# Solenoid_Drivers.net
KiCad netlist of a schematic drawn in Altium Designer
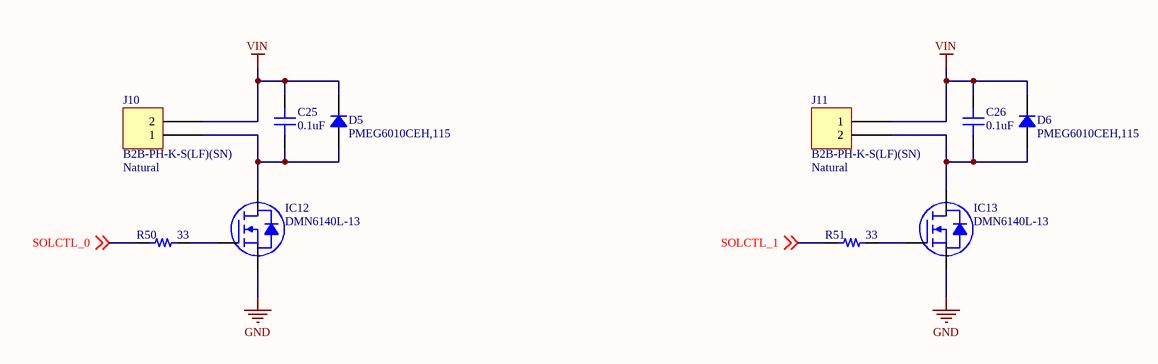
[diagram p0: Solenoid Drivers.SchDoc]

(export (version "E")
  (design (tool "Eeschema 10.0.6"))
  (components
    (comp (ref "C25")
      (value "0.1uF")
      (footprint "CAP 0603/1608")
      (description "CAP CER 0.1UF 50V X7R 0603")
      (fields
        (field (name "PART NUMBER") "CL10B104JB8NNNC")
        (field (name "MANUFACTURER") "Samsung Electro-Mechanics America, Inc.")
      )
      (libsource (lib "Celestial Library Database") (part "Capacitor"))
    )
    (comp (ref "C26")
      (value "0.1uF")
      (footprint "CAP 0603/1608")
      (description "CAP CER 0.1UF 50V X7R 0603")
      (fields
        (field (name "PART NUMBER") "CL10B104JB8NNNC")
        (field (name "MANUFACTURER") "Samsung Electro-Mechanics America, Inc.")
      )
      (libsource (lib "Celestial Library Database") (part "Capacitor"))
    )
    (comp (ref "D5")
      (value "PMEG6010CEH,115")
      (footprint "SOD123F")
      (description "DIODE SCHOTTKY 60V 1A SOD123F")
      (fields (field (name "MANUFACTURER") "NXP USA Inc."))
      (libsource (lib "Celestial Library Database") (part "Diode"))
    )
    (comp (ref "D6")
      (value "PMEG6010CEH,115")
      (footprint "SOD123F")
      (description "DIODE SCHOTTKY 60V 1A SOD123F")
      (fields (field (name "MANUFACTURER") "NXP USA Inc."))
      (libsource (lib "Celestial Library Database") (part "Diode"))
    )
    (comp (ref "IC12")
      (value "DMN6140L-13")
      (footprint "DIODES SOT-23-3")
      (description "MOSFET N-CH 60V 1.6A SOT23")
      (fields (field (name "MANUFACTURER") "Diodes Incorporated"))
      (libsource (lib "Celestial Library Database") (part "DIODES INC MOSFET N-CH SOT-23-3"))
    )
    (comp (ref "IC13")
      (value "DMN6140L-13")
      (footprint "DIODES SOT-23-3")
      (description "MOSFET N-CH 60V 1.6A SOT23")
      (fields (field (name "MANUFACTURER") "Diodes Incorporated"))
      (libsource (lib "Celestial Library Database") (part "DIODES INC MOSFET N-CH SOT-23-3"))
    )
    (comp (ref "J10")
      (value "B2B-PH-K-S(LF)(SN)")
      (footprint "JST B2B-PH-K")
      (description "CONN HEADER PH TOP 2POS 2MM")
      (fields (field (name "COLOUR") "Natural") (field (name "MANUFACTURER") "JST Sales America Inc."))
      (libsource (lib "Celestial Library Database") (part "2 Pin"))
    )
    (comp (ref "J11")
      (value "B2B-PH-K-S(LF)(SN)")
      (footprint "JST B2B-PH-K")
      (description "CONN HEADER PH TOP 2POS 2MM")
      (fields (field (name "COLOUR") "Natural") (field (name "MANUFACTURER") "JST Sales America Inc."))
      (libsource (lib "") (part "2 Pin_1"))
    )
    (comp (ref "R50")
      (value "33")
      (footprint "RES 0603/1608")
      (description "RES SMD 33 OHM 1% 1/10W 0603")
      (fields
        (field (name "PART NUMBER") "ERJ-3EKF33R0V")
        (field (name "MANUFACTURER") "Panasonic Electronic Components")
      )
      (libsource (lib "Celestial Library Database") (part "Resistor"))
    )
    (comp (ref "R51")
      (value "33")
      (footprint "RES 0603/1608")
      (description "RES SMD 33 OHM 1% 1/10W 0603")
      (fields
        (field (name "PART NUMBER") "ERJ-3EKF33R0V")
        (field (name "MANUFACTURER") "Panasonic Electronic Components")
      )
      (libsource (lib "Celestial Library Database") (part "Resistor"))
    )
  )
  (nets
    (net (code "1") (name "GND") (class "Default")
      (node (ref "IC12") (pin "3") (pinfunction "S_3") (pintype "passive"))
      (node (ref "IC13") (pin "3") (pinfunction "S_3") (pintype "passive"))
    )
    (net (code "2") (name "Net-(IC12-D)") (class "Default")
      (node (ref "C25") (pin "2") (pinfunction "2_2") (pintype "passive"))
      (node (ref "D5") (pin "1") (pinfunction "1_1") (pintype "passive"))
      (node (ref "IC12") (pin "2") (pinfunction "D_2") (pintype "passive"))
      (node (ref "J10") (pin "1") (pinfunction "1_1") (pintype "passive"))
    )
    (net (code "3") (name "Net-(IC12-G)") (class "Default")
      (node (ref "IC12") (pin "1") (pinfunction "G_1") (pintype "passive"))
      (node (ref "R50") (pin "2") (pinfunction "2_2") (pintype "passive"))
    )
    (net (code "4") (name "Net-(IC13-D)") (class "Default")
      (node (ref "C26") (pin "2") (pinfunction "2_2") (pintype "passive"))
      (node (ref "D6") (pin "1") (pinfunction "1_1") (pintype "passive"))
      (node (ref "IC13") (pin "2") (pinfunction "D_2") (pintype "passive"))
      (node (ref "J11") (pin "2") (pinfunction "2_2") (pintype "passive"))
    )
    (net (code "5") (name "Net-(IC13-G)") (class "Default")
      (node (ref "IC13") (pin "1") (pinfunction "G_1") (pintype "passive"))
      (node (ref "R51") (pin "2") (pinfunction "2_2") (pintype "passive"))
    )
    (net (code "6") (name "SOLCTL_0") (class "Default")
      (node (ref "R50") (pin "1") (pinfunction "1_1") (pintype "passive"))
    )
    (net (code "7") (name "SOLCTL_1") (class "Default")
      (node (ref "R51") (pin "1") (pinfunction "1_1") (pintype "passive"))
    )
    (net (code "8") (name "VIN") (class "Default")
      (node (ref "C25") (pin "1") (pinfunction "1_1") (pintype "passive"))
      (node (ref "C26") (pin "1") (pinfunction "1_1") (pintype "passive"))
      (node (ref "D5") (pin "2") (pinfunction "2_2") (pintype "passive"))
      (node (ref "D6") (pin "2") (pinfunction "2_2") (pintype "passive"))
      (node (ref "J10") (pin "2") (pinfunction "2_2") (pintype "passive"))
      (node (ref "J11") (pin "1") (pinfunction "1_1") (pintype "passive"))
    )
  )
)
